# tumkibot_new.net
KiCad netlist of a schematic drawn in EasyEDA Pro
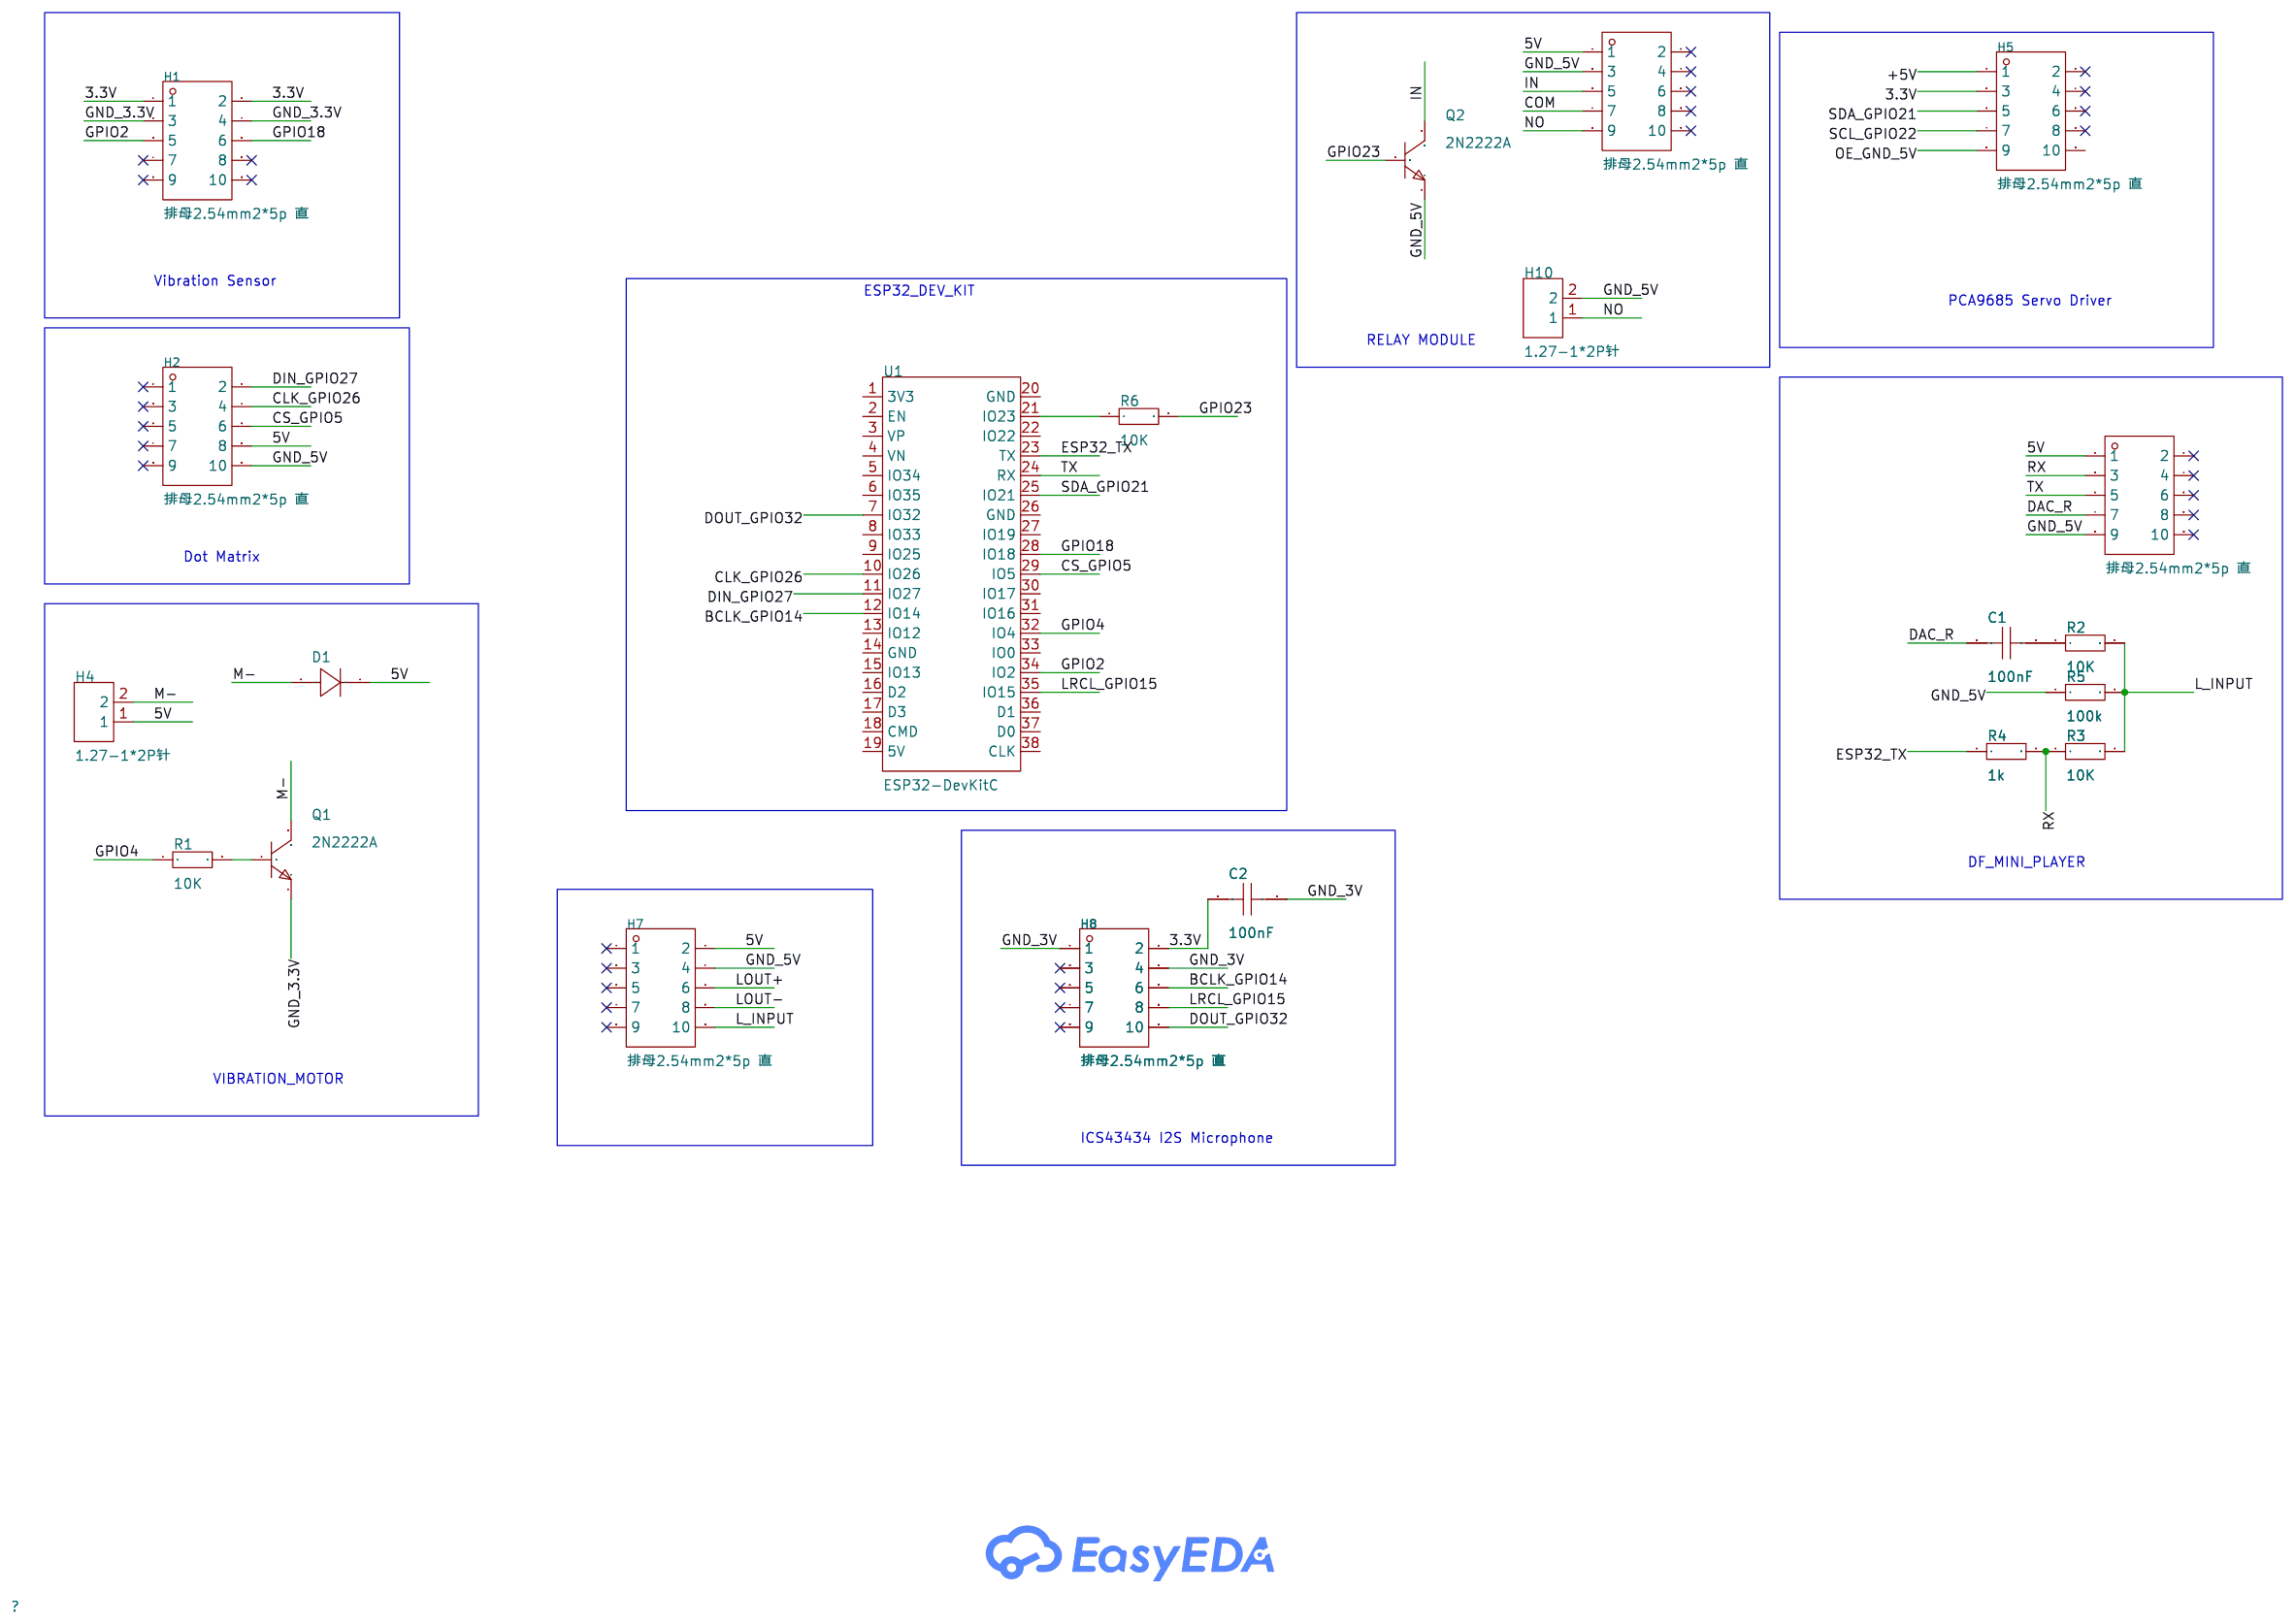
[diagram p0: schematic sheet]

(export (version "E")
  (design (tool "Eeschema 10.0.6"))
  (components
    (comp (ref "C1")
      (value "100nF")
      (footprint "easyedapro:C0603")
      (libsource (lib "easyedapro") (part "CAP"))
    )
    (comp (ref "C2")
      (value "100nF")
      (footprint "easyedapro:C0603")
      (libsource (lib "easyedapro") (part "CAP"))
    )
    (comp (ref "D1")
      (value "~")
      (footprint "easyedapro:SMA_L4.4-W2.8-LS5.4-RD")
      (libsource (lib "easyedapro") (part "D_1N4007"))
    )
    (comp (ref "H1")
      (value "排母2.54mm2*5p 直")
      (footprint "easyedapro:HDR-TH_10P-P2.54-V-F-R2-C5-S2.54")
      (fields (field (name "Manufacturer") "BOOMELE(博穆精密)"))
      (libsource (lib "easyedapro") (part "Female header2.54mm2*5p Straight"))
    )
    (comp (ref "H2")
      (value "排母2.54mm2*5p 直")
      (footprint "easyedapro:HDR-TH_10P-P2.54-V-F-R2-C5-S2.54")
      (fields (field (name "Manufacturer") "BOOMELE(博穆精密)"))
      (libsource (lib "easyedapro") (part "Female header2.54mm2*5p Straight"))
    )
    (comp (ref "H4")
      (value "1.27-1*2P针")
      (footprint "easyedapro:HDR-TH_2P-P1.27-V-M")
      (fields (field (name "Manufacturer") "BOOMELE(博穆精密)"))
      (libsource (lib "easyedapro") (part "1.27MM/1*2P"))
    )
    (comp (ref "H5")
      (value "排母2.54mm2*5p 直")
      (footprint "easyedapro:HDR-TH_10P-P2.54-V-F-R2-C5-S2.54")
      (fields (field (name "Manufacturer") "BOOMELE(博穆精密)"))
      (libsource (lib "easyedapro") (part "Female header2.54mm2*5p Straight"))
    )
    (comp (ref "H6")
      (value "排母2.54mm2*5p 直")
      (footprint "easyedapro:HDR-TH_10P-P2.54-V-F-R2-C5-S2.54")
      (fields (field (name "Manufacturer") "BOOMELE(博穆精密)"))
      (libsource (lib "easyedapro") (part "Female header2.54mm2*5p Straight"))
    )
    (comp (ref "H7")
      (value "排母2.54mm2*5p 直")
      (footprint "easyedapro:HDR-TH_10P-P2.54-V-F-R2-C5-S2.54")
      (fields (field (name "Manufacturer") "BOOMELE(博穆精密)"))
      (libsource (lib "easyedapro") (part "Female header2.54mm2*5p Straight"))
    )
    (comp (ref "H8")
      (value "排母2.54mm2*5p 直")
      (footprint "easyedapro:HDR-TH_10P-P2.54-V-F-R2-C5-S2.54")
      (fields (field (name "Manufacturer") "BOOMELE(博穆精密)"))
      (libsource (lib "easyedapro") (part "Female header2.54mm2*5p Straight"))
    )
    (comp (ref "H9")
      (value "排母2.54mm2*5p 直")
      (footprint "easyedapro:HDR-TH_10P-P2.54-V-F-R2-C5-S2.54")
      (fields (field (name "Manufacturer") "BOOMELE(博穆精密)"))
      (libsource (lib "easyedapro") (part "Female header2.54mm2*5p Straight"))
    )
    (comp (ref "H10")
      (value "1.27-1*2P针")
      (footprint "easyedapro:HDR-TH_2P-P1.27-V-M")
      (fields (field (name "Manufacturer") "BOOMELE(博穆精密)"))
      (libsource (lib "easyedapro") (part "1.27MM/1*2P"))
    )
    (comp (ref "Q1")
      (value "2N2222A")
      (footprint "easyedapro:TO-92-3_L4.5-W3.5-P1.27-L")
      (fields (field (name "Manufacturer") "HXY MOSFET(华轩阳电子)"))
      (libsource (lib "easyedapro") (part "2N2222A_C20616319"))
    )
    (comp (ref "Q2")
      (value "2N2222A")
      (footprint "easyedapro:TO-92-3_L4.5-W3.5-P1.27-L")
      (fields (field (name "Manufacturer") "HXY MOSFET(华轩阳电子)"))
      (libsource (lib "easyedapro") (part "2N2222A_C20616319"))
    )
    (comp (ref "R1") (value "10K") (footprint "easyedapro:R0603") (libsource (lib "easyedapro") (part "Res")))
    (comp (ref "R2") (value "10K") (footprint "easyedapro:R0603") (libsource (lib "easyedapro") (part "Res")))
    (comp (ref "R3") (value "10K") (footprint "easyedapro:R0603") (libsource (lib "easyedapro") (part "Res")))
    (comp (ref "R4") (value "10K") (footprint "easyedapro:R0603") (libsource (lib "easyedapro") (part "Res")))
    (comp (ref "R5") (value "10K") (footprint "easyedapro:R0603") (libsource (lib "easyedapro") (part "Res")))
    (comp (ref "R6") (value "10K") (footprint "easyedapro:R0603") (libsource (lib "easyedapro") (part "Res")))
    (comp (ref "U1")
      (value "ESP32-DevKitC")
      (footprint "easyedapro:BULETM-SMD_ESP32-DEVKITC")
      (fields (field (name "Manufacturer") "ESPRESSIF(乐鑫)"))
      (libsource (lib "easyedapro") (part "ESP32-DEVKITC"))
    )
  )
  (nets
    (net (code "1") (name "/+5V") (class "Default")
      (node (ref "H5") (pin "1") (pinfunction "1_1") (pintype "input"))
    )
    (net (code "2") (name "/3.3V") (class "Default")
      (node (ref "C2") (pin "2") (pinfunction "2_2") (pintype "input"))
      (node (ref "H1") (pin "1") (pinfunction "1_1") (pintype "input"))
      (node (ref "H1") (pin "2") (pinfunction "2_2") (pintype "input"))
      (node (ref "H5") (pin "3") (pinfunction "3_3") (pintype "input"))
      (node (ref "H8") (pin "2") (pinfunction "2_2") (pintype "input"))
    )
    (net (code "3") (name "/5V") (class "Default")
      (node (ref "D1") (pin "1") (pinfunction "K_1") (pintype "input"))
      (node (ref "H2") (pin "8") (pinfunction "8_8") (pintype "input"))
      (node (ref "H4") (pin "1") (pinfunction "1_1") (pintype "unspecified"))
      (node (ref "H6") (pin "1") (pinfunction "1_1") (pintype "input"))
      (node (ref "H7") (pin "2") (pinfunction "2_2") (pintype "input"))
      (node (ref "H9") (pin "1") (pinfunction "1_1") (pintype "input"))
    )
    (net (code "4") (name "/BCLK_GPIO14") (class "Default")
      (node (ref "H8") (pin "6") (pinfunction "6_6") (pintype "input"))
      (node (ref "U1") (pin "12") (pinfunction "IO14_12") (pintype "unspecified"))
    )
    (net (code "5") (name "/CLK_GPIO26") (class "Default")
      (node (ref "H2") (pin "4") (pinfunction "4_4") (pintype "input"))
      (node (ref "U1") (pin "10") (pinfunction "IO26_10") (pintype "unspecified"))
    )
    (net (code "6") (name "/COM") (class "Default")
      (node (ref "H9") (pin "7") (pinfunction "7_7") (pintype "input"))
    )
    (net (code "7") (name "/CS_GPIO5") (class "Default")
      (node (ref "H2") (pin "6") (pinfunction "6_6") (pintype "input"))
      (node (ref "U1") (pin "29") (pinfunction "IO5_29") (pintype "unspecified"))
    )
    (net (code "8") (name "/DAC_R") (class "Default")
      (node (ref "C1") (pin "2") (pinfunction "2_2") (pintype "input"))
      (node (ref "H6") (pin "7") (pinfunction "7_7") (pintype "input"))
    )
    (net (code "9") (name "/DIN_GPIO27") (class "Default")
      (node (ref "H2") (pin "2") (pinfunction "2_2") (pintype "input"))
      (node (ref "U1") (pin "11") (pinfunction "IO27_11") (pintype "unspecified"))
    )
    (net (code "10") (name "/DOUT_GPIO32") (class "Default")
      (node (ref "H8") (pin "10") (pinfunction "10_10") (pintype "input"))
      (node (ref "U1") (pin "7") (pinfunction "IO32_7") (pintype "unspecified"))
    )
    (net (code "11") (name "/ESP32_TX") (class "Default")
      (node (ref "R4") (pin "1") (pinfunction "1_1") (pintype "input"))
      (node (ref "U1") (pin "23") (pinfunction "TX_23") (pintype "unspecified"))
    )
    (net (code "12") (name "/GND_3.3V") (class "Default")
      (node (ref "H1") (pin "3") (pinfunction "3_3") (pintype "input"))
      (node (ref "H1") (pin "4") (pinfunction "4_4") (pintype "input"))
      (node (ref "Q1") (pin "1") (pinfunction "E_1") (pintype "unspecified"))
    )
    (net (code "13") (name "/GND_3V") (class "Default")
      (node (ref "C2") (pin "1") (pinfunction "1_1") (pintype "input"))
      (node (ref "H8") (pin "1") (pinfunction "1_1") (pintype "input"))
      (node (ref "H8") (pin "4") (pinfunction "4_4") (pintype "input"))
    )
    (net (code "14") (name "/GND_5V") (class "Default")
      (node (ref "H10") (pin "2") (pinfunction "2_2") (pintype "unspecified"))
      (node (ref "H2") (pin "10") (pinfunction "10_10") (pintype "input"))
      (node (ref "H6") (pin "9") (pinfunction "9_9") (pintype "input"))
      (node (ref "H7") (pin "4") (pinfunction "4_4") (pintype "input"))
      (node (ref "H9") (pin "3") (pinfunction "3_3") (pintype "input"))
      (node (ref "Q2") (pin "1") (pinfunction "E_1") (pintype "unspecified"))
      (node (ref "R5") (pin "1") (pinfunction "1_1") (pintype "input"))
    )
    (net (code "15") (name "/GPIO2") (class "Default")
      (node (ref "H1") (pin "5") (pinfunction "5_5") (pintype "input"))
      (node (ref "U1") (pin "34") (pinfunction "IO2_34") (pintype "unspecified"))
    )
    (net (code "16") (name "/GPIO4") (class "Default")
      (node (ref "R1") (pin "1") (pinfunction "1_1") (pintype "input"))
      (node (ref "U1") (pin "32") (pinfunction "IO4_32") (pintype "unspecified"))
    )
    (net (code "17") (name "/GPIO18") (class "Default")
      (node (ref "H1") (pin "6") (pinfunction "6_6") (pintype "input"))
      (node (ref "U1") (pin "28") (pinfunction "IO18_28") (pintype "unspecified"))
    )
    (net (code "18") (name "/GPIO23") (class "Default")
      (node (ref "Q2") (pin "2") (pinfunction "B_2") (pintype "unspecified"))
      (node (ref "R6") (pin "2") (pinfunction "2_2") (pintype "input"))
    )
    (net (code "19") (name "/IN") (class "Default")
      (node (ref "H9") (pin "5") (pinfunction "5_5") (pintype "input"))
      (node (ref "Q2") (pin "3") (pinfunction "C_3") (pintype "unspecified"))
    )
    (net (code "20") (name "/LOUT+") (class "Default")
      (node (ref "H7") (pin "6") (pinfunction "6_6") (pintype "input"))
    )
    (net (code "21") (name "/LOUT-") (class "Default")
      (node (ref "H7") (pin "8") (pinfunction "8_8") (pintype "input"))
    )
    (net (code "22") (name "/LRCL_GPIO15") (class "Default")
      (node (ref "H8") (pin "8") (pinfunction "8_8") (pintype "input"))
      (node (ref "U1") (pin "35") (pinfunction "IO15_35") (pintype "unspecified"))
    )
    (net (code "23") (name "/L_INPUT") (class "Default")
      (node (ref "H7") (pin "10") (pinfunction "10_10") (pintype "input"))
      (node (ref "R2") (pin "2") (pinfunction "2_2") (pintype "input"))
      (node (ref "R3") (pin "2") (pinfunction "2_2") (pintype "input"))
      (node (ref "R5") (pin "2") (pinfunction "2_2") (pintype "input"))
    )
    (net (code "24") (name "/M-") (class "Default")
      (node (ref "D1") (pin "2") (pinfunction "A_2") (pintype "input"))
      (node (ref "H4") (pin "2") (pinfunction "2_2") (pintype "unspecified"))
      (node (ref "Q1") (pin "3") (pinfunction "C_3") (pintype "unspecified"))
    )
    (net (code "25") (name "/NO") (class "Default")
      (node (ref "H10") (pin "1") (pinfunction "1_1") (pintype "unspecified"))
      (node (ref "H9") (pin "9") (pinfunction "9_9") (pintype "input"))
    )
    (net (code "26") (name "/OE_GND_5V") (class "Default")
      (node (ref "H5") (pin "9") (pinfunction "9_9") (pintype "input"))
    )
    (net (code "27") (name "/RX") (class "Default")
      (node (ref "H6") (pin "3") (pinfunction "3_3") (pintype "input"))
      (node (ref "R3") (pin "1") (pinfunction "1_1") (pintype "input"))
      (node (ref "R4") (pin "2") (pinfunction "2_2") (pintype "input"))
    )
    (net (code "28") (name "/SCL_GPIO22") (class "Default")
      (node (ref "H5") (pin "7") (pinfunction "7_7") (pintype "input"))
    )
    (net (code "29") (name "/SDA_GPIO21") (class "Default")
      (node (ref "H5") (pin "5") (pinfunction "5_5") (pintype "input"))
      (node (ref "U1") (pin "25") (pinfunction "IO21_25") (pintype "unspecified"))
    )
    (net (code "30") (name "/TX") (class "Default")
      (node (ref "H6") (pin "5") (pinfunction "5_5") (pintype "input"))
      (node (ref "U1") (pin "24") (pinfunction "RX_24") (pintype "unspecified"))
    )
    (net (code "31") (name "Net-(C1-Pad1)") (class "Default")
      (node (ref "C1") (pin "1") (pinfunction "1_1") (pintype "input"))
      (node (ref "R2") (pin "1") (pinfunction "1_1") (pintype "input"))
    )
    (net (code "32") (name "Net-(Q1-B)") (class "Default")
      (node (ref "Q1") (pin "2") (pinfunction "B_2") (pintype "unspecified"))
      (node (ref "R1") (pin "2") (pinfunction "2_2") (pintype "input"))
    )
    (net (code "33") (name "Net-(U1-IO23)") (class "Default")
      (node (ref "R6") (pin "1") (pinfunction "1_1") (pintype "input"))
      (node (ref "U1") (pin "21") (pinfunction "IO23_21") (pintype "unspecified"))
    )
    (net (code "34") (name "unconnected-(H1-Pad7)") (class "Default")
      (node (ref "H1") (pin "7") (pinfunction "7_7") (pintype "input+no_connect"))
    )
    (net (code "35") (name "unconnected-(H1-Pad8)") (class "Default")
      (node (ref "H1") (pin "8") (pinfunction "8_8") (pintype "input+no_connect"))
    )
    (net (code "36") (name "unconnected-(H1-Pad9)") (class "Default")
      (node (ref "H1") (pin "9") (pinfunction "9_9") (pintype "input+no_connect"))
    )
    (net (code "37") (name "unconnected-(H1-Pad10)") (class "Default")
      (node (ref "H1") (pin "10") (pinfunction "10_10") (pintype "input+no_connect"))
    )
    (net (code "38") (name "unconnected-(H2-Pad1)") (class "Default")
      (node (ref "H2") (pin "1") (pinfunction "1_1") (pintype "input+no_connect"))
    )
    (net (code "39") (name "unconnected-(H2-Pad3)") (class "Default")
      (node (ref "H2") (pin "3") (pinfunction "3_3") (pintype "input+no_connect"))
    )
    (net (code "40") (name "unconnected-(H2-Pad5)") (class "Default")
      (node (ref "H2") (pin "5") (pinfunction "5_5") (pintype "input+no_connect"))
    )
    (net (code "41") (name "unconnected-(H2-Pad7)") (class "Default")
      (node (ref "H2") (pin "7") (pinfunction "7_7") (pintype "input+no_connect"))
    )
    (net (code "42") (name "unconnected-(H2-Pad9)") (class "Default")
      (node (ref "H2") (pin "9") (pinfunction "9_9") (pintype "input+no_connect"))
    )
    (net (code "43") (name "unconnected-(H5-Pad2)") (class "Default")
      (node (ref "H5") (pin "2") (pinfunction "2_2") (pintype "input+no_connect"))
    )
    (net (code "44") (name "unconnected-(H5-Pad4)") (class "Default")
      (node (ref "H5") (pin "4") (pinfunction "4_4") (pintype "input+no_connect"))
    )
    (net (code "45") (name "unconnected-(H5-Pad6)") (class "Default")
      (node (ref "H5") (pin "6") (pinfunction "6_6") (pintype "input+no_connect"))
    )
    (net (code "46") (name "unconnected-(H5-Pad8)") (class "Default")
      (node (ref "H5") (pin "8") (pinfunction "8_8") (pintype "input+no_connect"))
    )
    (net (code "47") (name "unconnected-(H5-Pad10)") (class "Default")
      (node (ref "H5") (pin "10") (pinfunction "10_10") (pintype "input"))
    )
    (net (code "48") (name "unconnected-(H6-Pad2)") (class "Default")
      (node (ref "H6") (pin "2") (pinfunction "2_2") (pintype "input+no_connect"))
    )
    (net (code "49") (name "unconnected-(H6-Pad4)") (class "Default")
      (node (ref "H6") (pin "4") (pinfunction "4_4") (pintype "input+no_connect"))
    )
    (net (code "50") (name "unconnected-(H6-Pad6)") (class "Default")
      (node (ref "H6") (pin "6") (pinfunction "6_6") (pintype "input+no_connect"))
    )
    (net (code "51") (name "unconnected-(H6-Pad8)") (class "Default")
      (node (ref "H6") (pin "8") (pinfunction "8_8") (pintype "input+no_connect"))
    )
    (net (code "52") (name "unconnected-(H6-Pad10)") (class "Default")
      (node (ref "H6") (pin "10") (pinfunction "10_10") (pintype "input+no_connect"))
    )
    (net (code "53") (name "unconnected-(H7-Pad1)") (class "Default")
      (node (ref "H7") (pin "1") (pinfunction "1_1") (pintype "input+no_connect"))
    )
    (net (code "54") (name "unconnected-(H7-Pad3)") (class "Default")
      (node (ref "H7") (pin "3") (pinfunction "3_3") (pintype "input+no_connect"))
    )
    (net (code "55") (name "unconnected-(H7-Pad5)") (class "Default")
      (node (ref "H7") (pin "5") (pinfunction "5_5") (pintype "input+no_connect"))
    )
    (net (code "56") (name "unconnected-(H7-Pad7)") (class "Default")
      (node (ref "H7") (pin "7") (pinfunction "7_7") (pintype "input+no_connect"))
    )
    (net (code "57") (name "unconnected-(H7-Pad9)") (class "Default")
      (node (ref "H7") (pin "9") (pinfunction "9_9") (pintype "input+no_connect"))
    )
    (net (code "58") (name "unconnected-(H8-Pad3)") (class "Default")
      (node (ref "H8") (pin "3") (pinfunction "3_3") (pintype "input+no_connect"))
    )
    (net (code "59") (name "unconnected-(H8-Pad5)") (class "Default")
      (node (ref "H8") (pin "5") (pinfunction "5_5") (pintype "input+no_connect"))
    )
    (net (code "60") (name "unconnected-(H8-Pad7)") (class "Default")
      (node (ref "H8") (pin "7") (pinfunction "7_7") (pintype "input+no_connect"))
    )
    (net (code "61") (name "unconnected-(H8-Pad9)") (class "Default")
      (node (ref "H8") (pin "9") (pinfunction "9_9") (pintype "input+no_connect"))
    )
    (net (code "62") (name "unconnected-(H9-Pad2)") (class "Default")
      (node (ref "H9") (pin "2") (pinfunction "2_2") (pintype "input+no_connect"))
    )
    (net (code "63") (name "unconnected-(H9-Pad4)") (class "Default")
      (node (ref "H9") (pin "4") (pinfunction "4_4") (pintype "input+no_connect"))
    )
    (net (code "64") (name "unconnected-(H9-Pad6)") (class "Default")
      (node (ref "H9") (pin "6") (pinfunction "6_6") (pintype "input+no_connect"))
    )
    (net (code "65") (name "unconnected-(H9-Pad8)") (class "Default")
      (node (ref "H9") (pin "8") (pinfunction "8_8") (pintype "input+no_connect"))
    )
    (net (code "66") (name "unconnected-(H9-Pad10)") (class "Default")
      (node (ref "H9") (pin "10") (pinfunction "10_10") (pintype "input+no_connect"))
    )
    (net (code "67") (name "unconnected-(U1-3V3-Pad1)") (class "Default")
      (node (ref "U1") (pin "1") (pinfunction "3V3_1") (pintype "unspecified"))
    )
    (net (code "68") (name "unconnected-(U1-5V-Pad19)") (class "Default")
      (node (ref "U1") (pin "19") (pinfunction "5V_19") (pintype "unspecified"))
    )
    (net (code "69") (name "unconnected-(U1-CLK-Pad38)") (class "Default")
      (node (ref "U1") (pin "38") (pinfunction "CLK_38") (pintype "unspecified"))
    )
    (net (code "70") (name "unconnected-(U1-CMD-Pad18)") (class "Default")
      (node (ref "U1") (pin "18") (pinfunction "CMD_18") (pintype "unspecified"))
    )
    (net (code "71") (name "unconnected-(U1-D0-Pad37)") (class "Default")
      (node (ref "U1") (pin "37") (pinfunction "D0_37") (pintype "unspecified"))
    )
    (net (code "72") (name "unconnected-(U1-D1-Pad36)") (class "Default")
      (node (ref "U1") (pin "36") (pinfunction "D1_36") (pintype "unspecified"))
    )
    (net (code "73") (name "unconnected-(U1-D2-Pad16)") (class "Default")
      (node (ref "U1") (pin "16") (pinfunction "D2_16") (pintype "unspecified"))
    )
    (net (code "74") (name "unconnected-(U1-D3-Pad17)") (class "Default")
      (node (ref "U1") (pin "17") (pinfunction "D3_17") (pintype "unspecified"))
    )
    (net (code "75") (name "unconnected-(U1-EN-Pad2)") (class "Default")
      (node (ref "U1") (pin "2") (pinfunction "EN_2") (pintype "unspecified"))
    )
    (net (code "76") (name "unconnected-(U1-GND-Pad14)") (class "Default")
      (node (ref "U1") (pin "14") (pinfunction "GND_14") (pintype "unspecified"))
    )
    (net (code "77") (name "unconnected-(U1-GND-Pad20)") (class "Default")
      (node (ref "U1") (pin "20") (pinfunction "GND_20") (pintype "unspecified"))
    )
    (net (code "78") (name "unconnected-(U1-GND-Pad26)") (class "Default")
      (node (ref "U1") (pin "26") (pinfunction "GND_26") (pintype "unspecified"))
    )
    (net (code "79") (name "unconnected-(U1-IO0-Pad33)") (class "Default")
      (node (ref "U1") (pin "33") (pinfunction "IO0_33") (pintype "unspecified"))
    )
    (net (code "80") (name "unconnected-(U1-IO12-Pad13)") (class "Default")
      (node (ref "U1") (pin "13") (pinfunction "IO12_13") (pintype "unspecified"))
    )
    (net (code "81") (name "unconnected-(U1-IO13-Pad15)") (class "Default")
      (node (ref "U1") (pin "15") (pinfunction "IO13_15") (pintype "unspecified"))
    )
    (net (code "82") (name "unconnected-(U1-IO16-Pad31)") (class "Default")
      (node (ref "U1") (pin "31") (pinfunction "IO16_31") (pintype "unspecified"))
    )
    (net (code "83") (name "unconnected-(U1-IO17-Pad30)") (class "Default")
      (node (ref "U1") (pin "30") (pinfunction "IO17_30") (pintype "unspecified"))
    )
    (net (code "84") (name "unconnected-(U1-IO19-Pad27)") (class "Default")
      (node (ref "U1") (pin "27") (pinfunction "IO19_27") (pintype "unspecified"))
    )
    (net (code "85") (name "unconnected-(U1-IO22-Pad22)") (class "Default")
      (node (ref "U1") (pin "22") (pinfunction "IO22_22") (pintype "unspecified"))
    )
    (net (code "86") (name "unconnected-(U1-IO25-Pad9)") (class "Default")
      (node (ref "U1") (pin "9") (pinfunction "IO25_9") (pintype "unspecified"))
    )
    (net (code "87") (name "unconnected-(U1-IO33-Pad8)") (class "Default")
      (node (ref "U1") (pin "8") (pinfunction "IO33_8") (pintype "unspecified"))
    )
    (net (code "88") (name "unconnected-(U1-IO34-Pad5)") (class "Default")
      (node (ref "U1") (pin "5") (pinfunction "IO34_5") (pintype "unspecified"))
    )
    (net (code "89") (name "unconnected-(U1-IO35-Pad6)") (class "Default")
      (node (ref "U1") (pin "6") (pinfunction "IO35_6") (pintype "unspecified"))
    )
    (net (code "90") (name "unconnected-(U1-VN-Pad4)") (class "Default")
      (node (ref "U1") (pin "4") (pinfunction "VN_4") (pintype "unspecified"))
    )
    (net (code "91") (name "unconnected-(U1-VP-Pad3)") (class "Default")
      (node (ref "U1") (pin "3") (pinfunction "VP_3") (pintype "unspecified"))
    )
  )
)
